# autolock.net
KiCad netlist of a schematic drawn in EAGLE
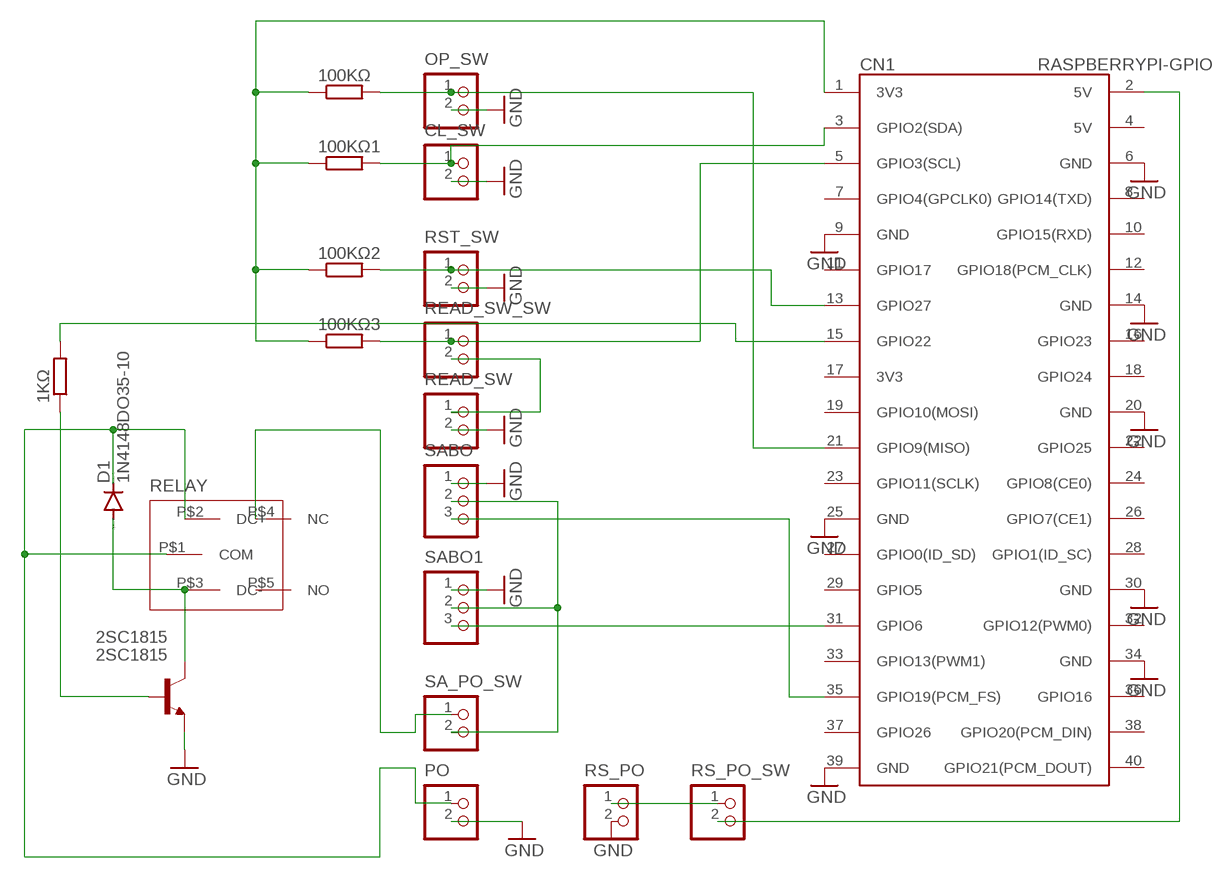
[diagram p0: schematic, sheet 1]

(export (version "E")
  (design (tool "Eeschema 10.0.6"))
  (components
    (comp (ref "1KΩ")
      (value "R-EU_0207/10")
      (footprint "eagle-import:0207_10")
      (libsource (lib "eagle-import") (part "R-EU_0207/10"))
    )
    (comp (ref "2SC1815")
      (value "2SC1815")
      (footprint "eagle-import:TO92-ECB")
      (libsource (lib "eagle-import") (part "2SC1815"))
    )
    (comp (ref "100KΩ")
      (value "R-EU_0207/10")
      (footprint "eagle-import:0207_10")
      (libsource (lib "eagle-import") (part "R-EU_0207/10"))
    )
    (comp (ref "100KΩ1")
      (value "R-EU_0207/10")
      (footprint "eagle-import:0207_10")
      (libsource (lib "eagle-import") (part "R-EU_0207/10"))
    )
    (comp (ref "100KΩ2")
      (value "R-EU_0207/10")
      (footprint "eagle-import:0207_10")
      (libsource (lib "eagle-import") (part "R-EU_0207/10"))
    )
    (comp (ref "100KΩ3")
      (value "R-EU_0207/10")
      (footprint "eagle-import:0207_10")
      (libsource (lib "eagle-import") (part "R-EU_0207/10"))
    )
    (comp (ref "CL_SW")
      (value "B2B-XH-A")
      (footprint "eagle-import:B2B-XH-A")
      (libsource (lib "eagle-import") (part "B2B-XH-A"))
    )
    (comp (ref "CN1")
      (value "RASPBERRYPI-GPIO")
      (footprint "eagle-import:2X20-BOLD")
      (libsource (lib "eagle-import") (part "RASPBERRYPI-GPIO"))
    )
    (comp (ref "D1")
      (value "1N4148DO35-10")
      (footprint "eagle-import:DO35-10")
      (libsource (lib "eagle-import") (part "1N4148DO35-10"))
    )
    (comp (ref "OP_SW")
      (value "B2B-XH-A")
      (footprint "eagle-import:B2B-XH-A")
      (libsource (lib "eagle-import") (part "B2B-XH-A"))
    )
    (comp (ref "PO")
      (value "B2B-XH-A")
      (footprint "eagle-import:B2B-XH-A")
      (libsource (lib "eagle-import") (part "B2B-XH-A"))
    )
    (comp (ref "READ_SW")
      (value "B2B-XH-A")
      (footprint "eagle-import:B2B-XH-A")
      (libsource (lib "eagle-import") (part "B2B-XH-A"))
    )
    (comp (ref "READ_SW_SW")
      (value "B2B-XH-A")
      (footprint "eagle-import:B2B-XH-A")
      (libsource (lib "eagle-import") (part "B2B-XH-A"))
    )
    (comp (ref "RELAY")
      (value "SRD05VDCSLC")
      (footprint "eagle-import:SRD05VDCSLC")
      (libsource (lib "eagle-import") (part "SRD05VDCSLC"))
    )
    (comp (ref "RST_SW")
      (value "B2B-XH-A")
      (footprint "eagle-import:B2B-XH-A")
      (libsource (lib "eagle-import") (part "B2B-XH-A"))
    )
    (comp (ref "RS_PO")
      (value "B2B-XH-A")
      (footprint "eagle-import:B2B-XH-A")
      (libsource (lib "eagle-import") (part "B2B-XH-A"))
    )
    (comp (ref "RS_PO_SW")
      (value "B2B-XH-A")
      (footprint "eagle-import:B2B-XH-A")
      (libsource (lib "eagle-import") (part "B2B-XH-A"))
    )
    (comp (ref "SABO")
      (value "B3B-XH-A")
      (footprint "eagle-import:B3B-XH-A")
      (libsource (lib "eagle-import") (part "B3B-XH-A"))
    )
    (comp (ref "SABO1")
      (value "B3B-XH-A")
      (footprint "eagle-import:B3B-XH-A")
      (libsource (lib "eagle-import") (part "B3B-XH-A"))
    )
    (comp (ref "SA_PO_SW")
      (value "B2B-XH-A")
      (footprint "eagle-import:B2B-XH-A")
      (libsource (lib "eagle-import") (part "B2B-XH-A"))
    )
  )
  (nets
    (net (code "1") (name "GND") (class "Default")
      (node (ref "2SC1815") (pin "E") (pinfunction "E_E") (pintype "passive"))
      (node (ref "CL_SW") (pin "2") (pinfunction "2_2") (pintype "passive"))
      (node (ref "CN1") (pin "14") (pinfunction "GND_14") (pintype "bidirectional"))
      (node (ref "CN1") (pin "20") (pinfunction "GND_20") (pintype "bidirectional"))
      (node (ref "CN1") (pin "25") (pinfunction "GND_25") (pintype "bidirectional"))
      (node (ref "CN1") (pin "30") (pinfunction "GND_30") (pintype "bidirectional"))
      (node (ref "CN1") (pin "34") (pinfunction "GND_34") (pintype "bidirectional"))
      (node (ref "CN1") (pin "39") (pinfunction "GND_39") (pintype "bidirectional"))
      (node (ref "CN1") (pin "6") (pinfunction "GND_6") (pintype "bidirectional"))
      (node (ref "CN1") (pin "9") (pinfunction "GND_9") (pintype "bidirectional"))
      (node (ref "OP_SW") (pin "2") (pinfunction "2_2") (pintype "passive"))
      (node (ref "PO") (pin "2") (pinfunction "2_2") (pintype "passive"))
      (node (ref "READ_SW") (pin "2") (pinfunction "2_2") (pintype "passive"))
      (node (ref "RST_SW") (pin "2") (pinfunction "2_2") (pintype "passive"))
      (node (ref "RS_PO") (pin "2") (pinfunction "2_2") (pintype "passive"))
      (node (ref "SABO") (pin "1") (pinfunction "1_1") (pintype "passive"))
      (node (ref "SABO1") (pin "1") (pinfunction "1_1") (pintype "passive"))
    )
    (net (code "2") (name "Net-(1KΩ-Pad1)") (class "Default")
      (node (ref "1KΩ") (pin "1") (pinfunction "1_1") (pintype "passive"))
      (node (ref "2SC1815") (pin "B") (pinfunction "B_B") (pintype "passive"))
    )
    (net (code "3") (name "Net-(100KΩ-Pad1)") (class "Default")
      (node (ref "100KΩ") (pin "1") (pinfunction "1_1") (pintype "passive"))
      (node (ref "100KΩ1") (pin "1") (pinfunction "1_1") (pintype "passive"))
      (node (ref "100KΩ2") (pin "1") (pinfunction "1_1") (pintype "passive"))
      (node (ref "100KΩ3") (pin "1") (pinfunction "1_1") (pintype "passive"))
      (node (ref "CN1") (pin "1") (pinfunction "3V3_1") (pintype "bidirectional"))
    )
    (net (code "4") (name "Net-(CN1-5V-Pad2)") (class "Default")
      (node (ref "CN1") (pin "2") (pinfunction "5V_2") (pintype "bidirectional"))
      (node (ref "RS_PO_SW") (pin "2") (pinfunction "2_2") (pintype "passive"))
    )
    (net (code "5") (name "Net-(CN1-GPIO2(SDA))") (class "Default")
      (node (ref "100KΩ1") (pin "2") (pinfunction "2_2") (pintype "passive"))
      (node (ref "CL_SW") (pin "1") (pinfunction "1_1") (pintype "passive"))
      (node (ref "CN1") (pin "3") (pinfunction "GPIO2(SDA)_3") (pintype "bidirectional"))
    )
    (net (code "6") (name "Net-(CN1-GPIO3(SCL))") (class "Default")
      (node (ref "100KΩ3") (pin "2") (pinfunction "2_2") (pintype "passive"))
      (node (ref "CN1") (pin "5") (pinfunction "GPIO3(SCL)_5") (pintype "bidirectional"))
      (node (ref "READ_SW_SW") (pin "1") (pinfunction "1_1") (pintype "passive"))
    )
    (net (code "7") (name "Net-(CN1-GPIO6)") (class "Default")
      (node (ref "CN1") (pin "31") (pinfunction "GPIO6_31") (pintype "bidirectional"))
      (node (ref "SABO1") (pin "3") (pinfunction "3_3") (pintype "passive"))
    )
    (net (code "8") (name "Net-(CN1-GPIO9(MISO))") (class "Default")
      (node (ref "100KΩ") (pin "2") (pinfunction "2_2") (pintype "passive"))
      (node (ref "CN1") (pin "21") (pinfunction "GPIO9(MISO)_21") (pintype "bidirectional"))
      (node (ref "OP_SW") (pin "1") (pinfunction "1_1") (pintype "passive"))
    )
    (net (code "9") (name "Net-(CN1-GPIO19(PCM_FS))") (class "Default")
      (node (ref "CN1") (pin "35") (pinfunction "GPIO19(PCM_FS)_35") (pintype "bidirectional"))
      (node (ref "SABO") (pin "3") (pinfunction "3_3") (pintype "passive"))
    )
    (net (code "10") (name "Net-(CN1-GPIO22)") (class "Default")
      (node (ref "1KΩ") (pin "2") (pinfunction "2_2") (pintype "passive"))
      (node (ref "CN1") (pin "15") (pinfunction "GPIO22_15") (pintype "bidirectional"))
    )
    (net (code "11") (name "Net-(CN1-GPIO27)") (class "Default")
      (node (ref "100KΩ2") (pin "2") (pinfunction "2_2") (pintype "passive"))
      (node (ref "CN1") (pin "13") (pinfunction "GPIO27_13") (pintype "bidirectional"))
      (node (ref "RST_SW") (pin "1") (pinfunction "1_1") (pintype "passive"))
    )
    (net (code "12") (name "Net-(READ_SW-Pad1)") (class "Default")
      (node (ref "READ_SW") (pin "1") (pinfunction "1_1") (pintype "passive"))
      (node (ref "READ_SW_SW") (pin "2") (pinfunction "2_2") (pintype "passive"))
    )
    (net (code "13") (name "Net-(RELAY-COM)") (class "Default")
      (node (ref "D1") (pin "C") (pinfunction "C_C") (pintype "passive"))
      (node (ref "PO") (pin "1") (pinfunction "1_1") (pintype "passive"))
      (node (ref "RELAY") (pin "P$1") (pinfunction "COM_P$1") (pintype "bidirectional"))
      (node (ref "RELAY") (pin "P$2") (pinfunction "DC+_P$2") (pintype "bidirectional"))
    )
    (net (code "14") (name "Net-(RELAY-DC-)") (class "Default")
      (node (ref "2SC1815") (pin "C") (pinfunction "C_C") (pintype "passive"))
      (node (ref "D1") (pin "A") (pinfunction "A_A") (pintype "passive"))
      (node (ref "RELAY") (pin "P$3") (pinfunction "DC-_P$3") (pintype "bidirectional"))
    )
    (net (code "15") (name "Net-(RELAY-NC)") (class "Default")
      (node (ref "RELAY") (pin "P$4") (pinfunction "NC_P$4") (pintype "bidirectional"))
      (node (ref "SA_PO_SW") (pin "1") (pinfunction "1_1") (pintype "passive"))
    )
    (net (code "16") (name "Net-(RS_PO-Pad1)") (class "Default")
      (node (ref "RS_PO") (pin "1") (pinfunction "1_1") (pintype "passive"))
      (node (ref "RS_PO_SW") (pin "1") (pinfunction "1_1") (pintype "passive"))
    )
    (net (code "17") (name "Net-(SABO-Pad2)") (class "Default")
      (node (ref "SABO") (pin "2") (pinfunction "2_2") (pintype "passive"))
      (node (ref "SABO1") (pin "2") (pinfunction "2_2") (pintype "passive"))
      (node (ref "SA_PO_SW") (pin "2") (pinfunction "2_2") (pintype "passive"))
    )
    (net (code "18") (name "unconnected-(CN1-3V3-Pad17)") (class "Default")
      (node (ref "CN1") (pin "17") (pinfunction "3V3_17") (pintype "bidirectional"))
    )
    (net (code "19") (name "unconnected-(CN1-5V-Pad4)") (class "Default")
      (node (ref "CN1") (pin "4") (pinfunction "5V_4") (pintype "bidirectional"))
    )
    (net (code "20") (name "unconnected-(CN1-GPIO0(ID_SD)-Pad27)") (class "Default")
      (node (ref "CN1") (pin "27") (pinfunction "GPIO0(ID_SD)_27") (pintype "bidirectional"))
    )
    (net (code "21") (name "unconnected-(CN1-GPIO1(ID_SC)-Pad28)") (class "Default")
      (node (ref "CN1") (pin "28") (pinfunction "GPIO1(ID_SC)_28") (pintype "bidirectional"))
    )
    (net (code "22") (name "unconnected-(CN1-GPIO4(GPCLK0)-Pad7)") (class "Default")
      (node (ref "CN1") (pin "7") (pinfunction "GPIO4(GPCLK0)_7") (pintype "bidirectional"))
    )
    (net (code "23") (name "unconnected-(CN1-GPIO5-Pad29)") (class "Default")
      (node (ref "CN1") (pin "29") (pinfunction "GPIO5_29") (pintype "bidirectional"))
    )
    (net (code "24") (name "unconnected-(CN1-GPIO7(CE1)-Pad26)") (class "Default")
      (node (ref "CN1") (pin "26") (pinfunction "GPIO7(CE1)_26") (pintype "bidirectional"))
    )
    (net (code "25") (name "unconnected-(CN1-GPIO8(CE0)-Pad24)") (class "Default")
      (node (ref "CN1") (pin "24") (pinfunction "GPIO8(CE0)_24") (pintype "bidirectional"))
    )
    (net (code "26") (name "unconnected-(CN1-GPIO10(MOSI)-Pad19)") (class "Default")
      (node (ref "CN1") (pin "19") (pinfunction "GPIO10(MOSI)_19") (pintype "bidirectional"))
    )
    (net (code "27") (name "unconnected-(CN1-GPIO11(SCLK)-Pad23)") (class "Default")
      (node (ref "CN1") (pin "23") (pinfunction "GPIO11(SCLK)_23") (pintype "bidirectional"))
    )
    (net (code "28") (name "unconnected-(CN1-GPIO12(PWM0)-Pad32)") (class "Default")
      (node (ref "CN1") (pin "32") (pinfunction "GPIO12(PWM0)_32") (pintype "bidirectional"))
    )
    (net (code "29") (name "unconnected-(CN1-GPIO13(PWM1)-Pad33)") (class "Default")
      (node (ref "CN1") (pin "33") (pinfunction "GPIO13(PWM1)_33") (pintype "bidirectional"))
    )
    (net (code "30") (name "unconnected-(CN1-GPIO14(TXD)-Pad8)") (class "Default")
      (node (ref "CN1") (pin "8") (pinfunction "GPIO14(TXD)_8") (pintype "bidirectional"))
    )
    (net (code "31") (name "unconnected-(CN1-GPIO15(RXD)-Pad10)") (class "Default")
      (node (ref "CN1") (pin "10") (pinfunction "GPIO15(RXD)_10") (pintype "bidirectional"))
    )
    (net (code "32") (name "unconnected-(CN1-GPIO16-Pad36)") (class "Default")
      (node (ref "CN1") (pin "36") (pinfunction "GPIO16_36") (pintype "bidirectional"))
    )
    (net (code "33") (name "unconnected-(CN1-GPIO17-Pad11)") (class "Default")
      (node (ref "CN1") (pin "11") (pinfunction "GPIO17_11") (pintype "bidirectional"))
    )
    (net (code "34") (name "unconnected-(CN1-GPIO18(PCM_CLK)-Pad12)") (class "Default")
      (node (ref "CN1") (pin "12") (pinfunction "GPIO18(PCM_CLK)_12") (pintype "bidirectional"))
    )
    (net (code "35") (name "unconnected-(CN1-GPIO20(PCM_DIN)-Pad38)") (class "Default")
      (node (ref "CN1") (pin "38") (pinfunction "GPIO20(PCM_DIN)_38") (pintype "bidirectional"))
    )
    (net (code "36") (name "unconnected-(CN1-GPIO21(PCM_DOUT)-Pad40)") (class "Default")
      (node (ref "CN1") (pin "40") (pinfunction "GPIO21(PCM_DOUT)_40") (pintype "bidirectional"))
    )
    (net (code "37") (name "unconnected-(CN1-GPIO23-Pad16)") (class "Default")
      (node (ref "CN1") (pin "16") (pinfunction "GPIO23_16") (pintype "bidirectional"))
    )
    (net (code "38") (name "unconnected-(CN1-GPIO24-Pad18)") (class "Default")
      (node (ref "CN1") (pin "18") (pinfunction "GPIO24_18") (pintype "bidirectional"))
    )
    (net (code "39") (name "unconnected-(CN1-GPIO25-Pad22)") (class "Default")
      (node (ref "CN1") (pin "22") (pinfunction "GPIO25_22") (pintype "bidirectional"))
    )
    (net (code "40") (name "unconnected-(CN1-GPIO26-Pad37)") (class "Default")
      (node (ref "CN1") (pin "37") (pinfunction "GPIO26_37") (pintype "bidirectional"))
    )
    (net (code "41") (name "unconnected-(RELAY-NO-PadP$5)") (class "Default")
      (node (ref "RELAY") (pin "P$5") (pinfunction "NO_P$5") (pintype "bidirectional"))
    )
  )
)
